# VEX_Competition_Switch_Solo.net
KiCad netlist of a schematic drawn in EasyEDA
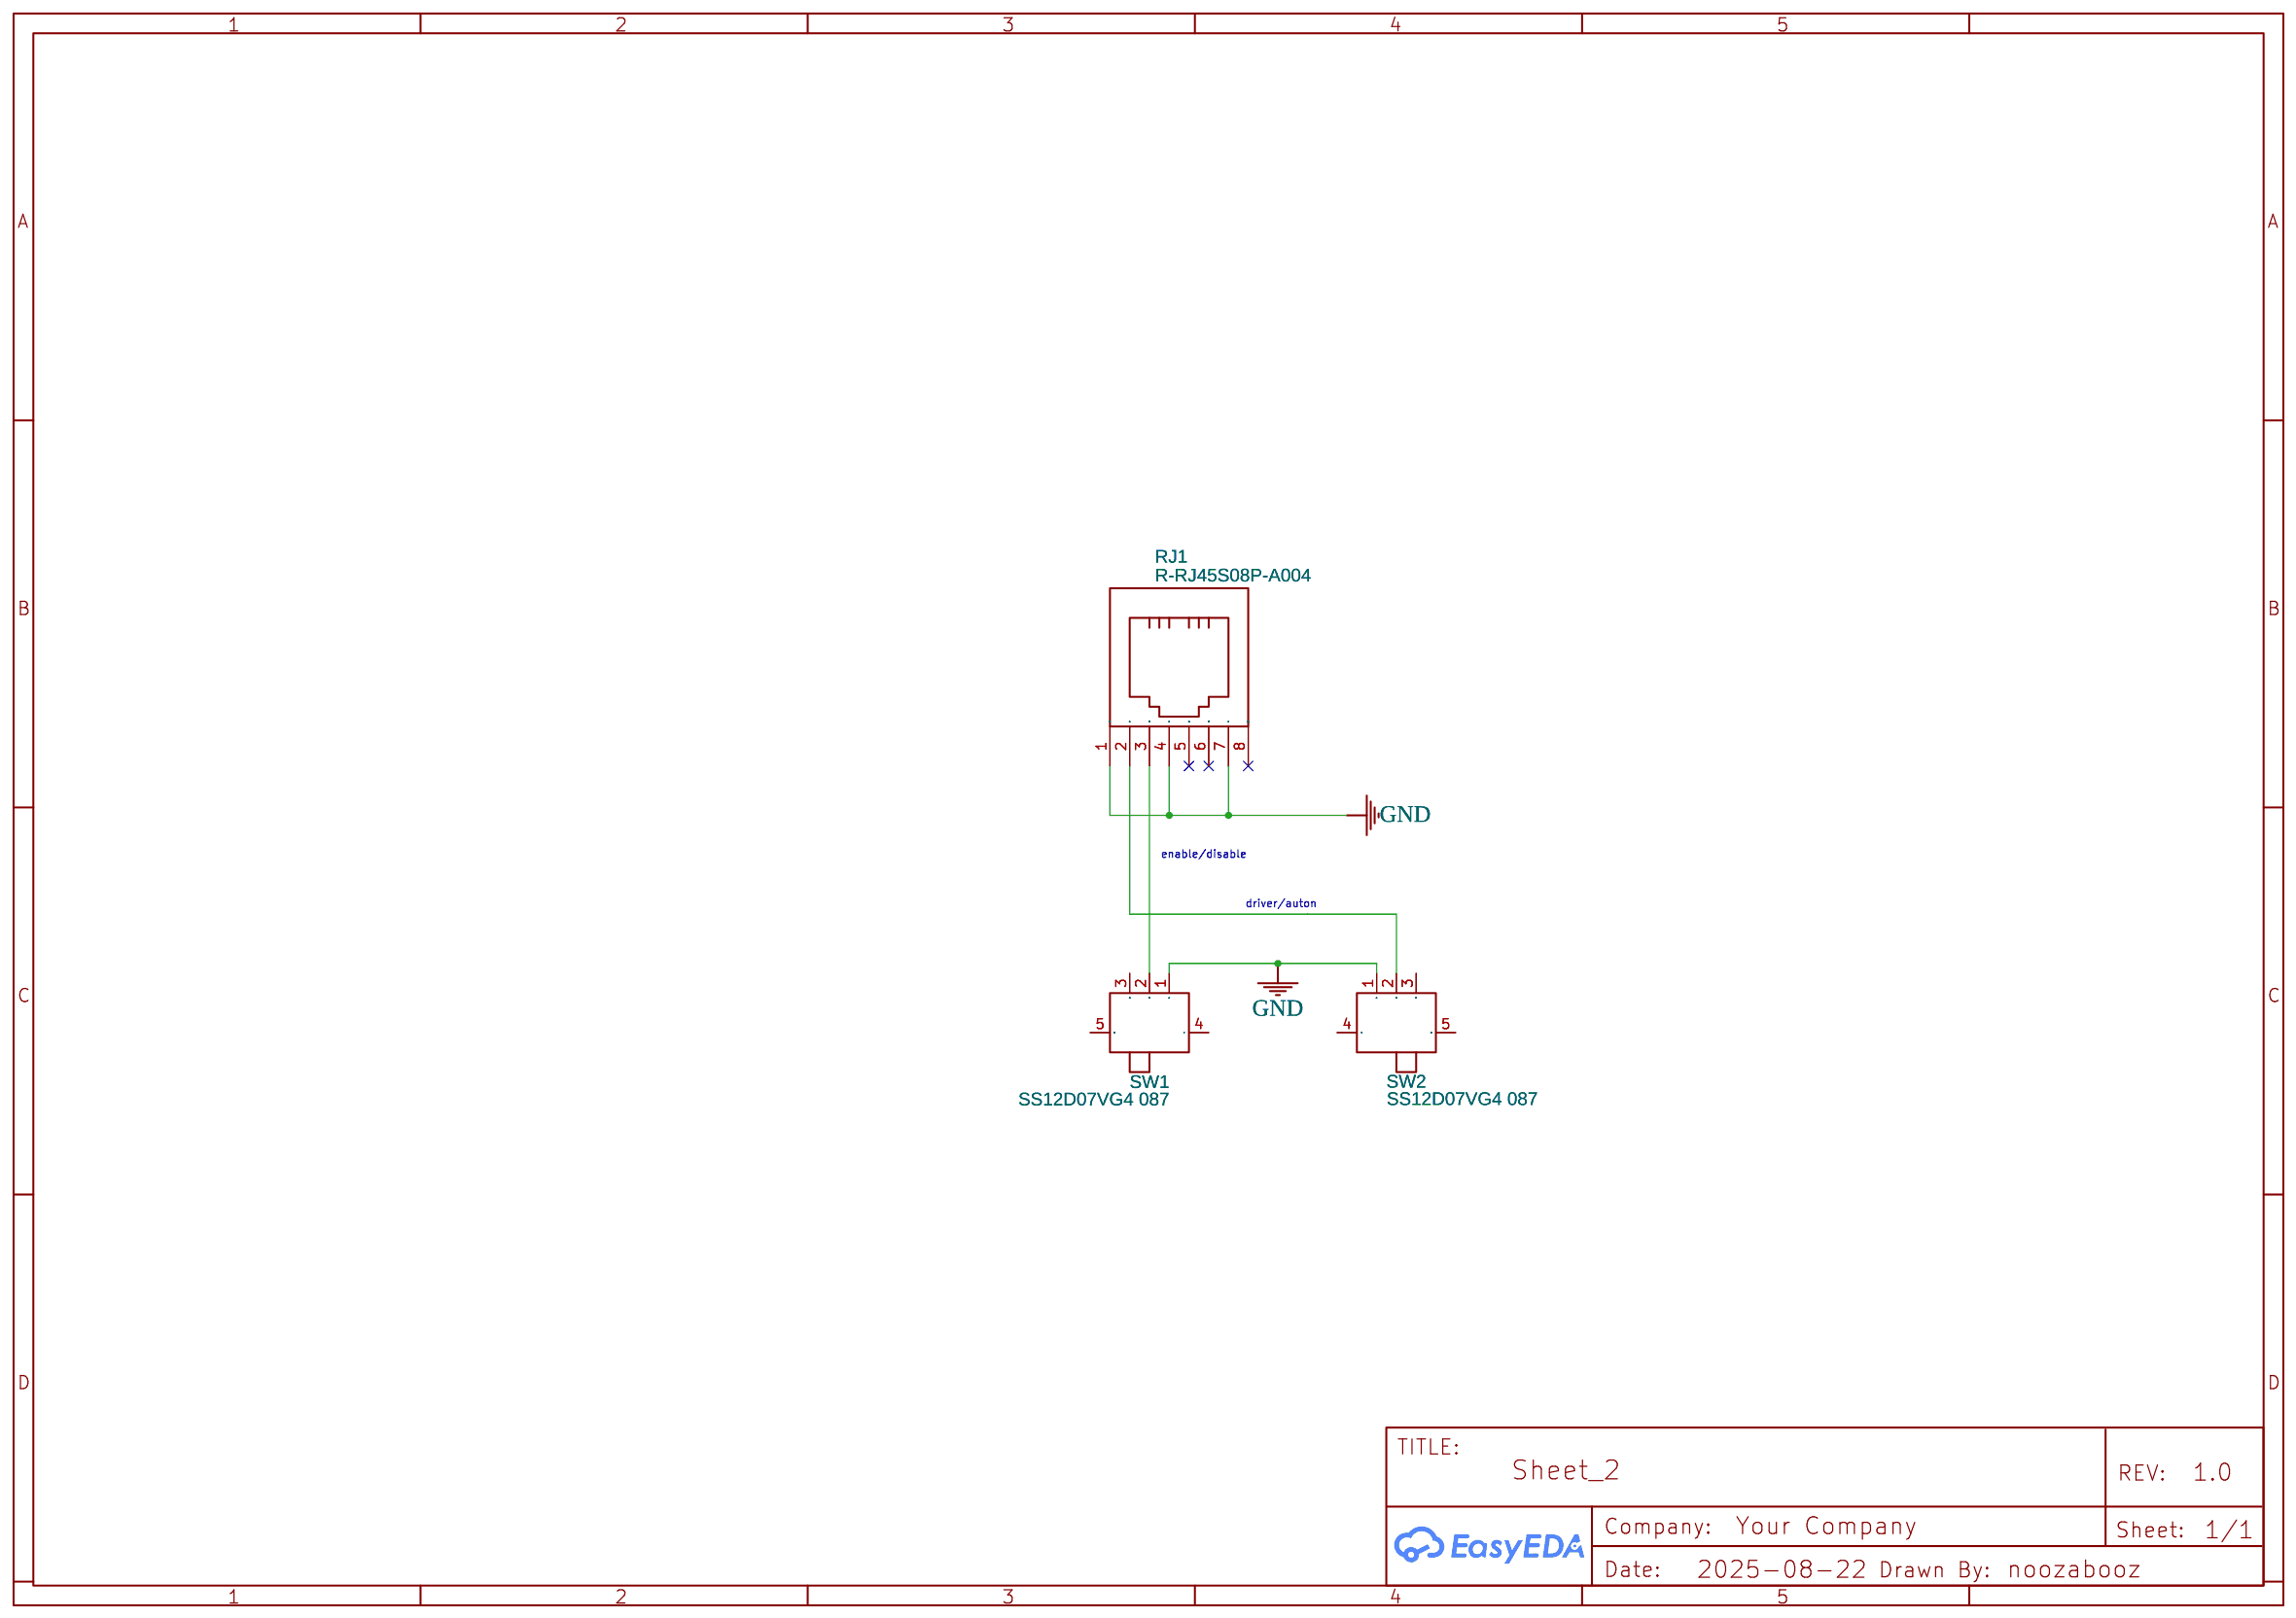
[diagram p0: schematic sheet]

(export (version "E")
  (design (tool "Eeschema 10.0.6"))
  (components
    (comp (ref "RJ1")
      (value "R-RJ45S08P-A004")
      (fields (field (name "Manufacturer") "Ckmtw(灿科盟)"))
      (libsource (lib "") (part "R-RJ45S08P-A004"))
    )
    (comp (ref "SW1")
      (value "SS12D07VG4 087")
      (fields (field (name "Manufacturer") "SHOU HAN(首韩)"))
      (libsource (lib "") (part "SS12D07VG4 087_1"))
    )
    (comp (ref "SW2")
      (value "SS12D07VG4 087")
      (fields (field (name "Manufacturer") "SHOU HAN(首韩)"))
      (libsource (lib "") (part "SS12D07VG4 087"))
    )
  )
  (nets
    (net (code "1") (name "GND") (class "Default")
      (node (ref "RJ1") (pin "1") (pinfunction "1_1") (pintype "unspecified"))
      (node (ref "RJ1") (pin "4") (pinfunction "4_4") (pintype "unspecified"))
      (node (ref "RJ1") (pin "7") (pinfunction "7_7") (pintype "unspecified"))
      (node (ref "SW1") (pin "1") (pinfunction "1_1") (pintype "unspecified"))
      (node (ref "SW2") (pin "1") (pinfunction "1_1") (pintype "unspecified"))
    )
    (net (code "2") (name "Net-(RJ1-Pad2)") (class "Default")
      (node (ref "RJ1") (pin "2") (pinfunction "2_2") (pintype "unspecified"))
      (node (ref "SW2") (pin "2") (pinfunction "2_2") (pintype "unspecified"))
    )
    (net (code "3") (name "Net-(RJ1-Pad3)") (class "Default")
      (node (ref "RJ1") (pin "3") (pinfunction "3_3") (pintype "unspecified"))
      (node (ref "SW1") (pin "2") (pinfunction "2_2") (pintype "unspecified"))
    )
    (net (code "4") (name "unconnected-(RJ1-Pad5)") (class "Default")
      (node (ref "RJ1") (pin "5") (pinfunction "5_5") (pintype "unspecified+no_connect"))
    )
    (net (code "5") (name "unconnected-(RJ1-Pad6)") (class "Default")
      (node (ref "RJ1") (pin "6") (pinfunction "6_6") (pintype "unspecified+no_connect"))
    )
    (net (code "6") (name "unconnected-(RJ1-Pad8)") (class "Default")
      (node (ref "RJ1") (pin "8") (pinfunction "8_8") (pintype "unspecified+no_connect"))
    )
    (net (code "7") (name "unconnected-(SW1-Pad3)") (class "Default")
      (node (ref "SW1") (pin "3") (pinfunction "3_3") (pintype "unspecified"))
    )
    (net (code "8") (name "unconnected-(SW1-Pad4)") (class "Default")
      (node (ref "SW1") (pin "4") (pinfunction "4_4") (pintype "unspecified"))
    )
    (net (code "9") (name "unconnected-(SW1-Pad5)") (class "Default")
      (node (ref "SW1") (pin "5") (pinfunction "5_5") (pintype "unspecified"))
    )
    (net (code "10") (name "unconnected-(SW2-Pad3)") (class "Default")
      (node (ref "SW2") (pin "3") (pinfunction "3_3") (pintype "unspecified"))
    )
    (net (code "11") (name "unconnected-(SW2-Pad4)") (class "Default")
      (node (ref "SW2") (pin "4") (pinfunction "4_4") (pintype "unspecified"))
    )
    (net (code "12") (name "unconnected-(SW2-Pad5)") (class "Default")
      (node (ref "SW2") (pin "5") (pinfunction "5_5") (pintype "unspecified"))
    )
  )
)
